# sra_board_2020.net
KiCad netlist of a schematic drawn in EAGLE
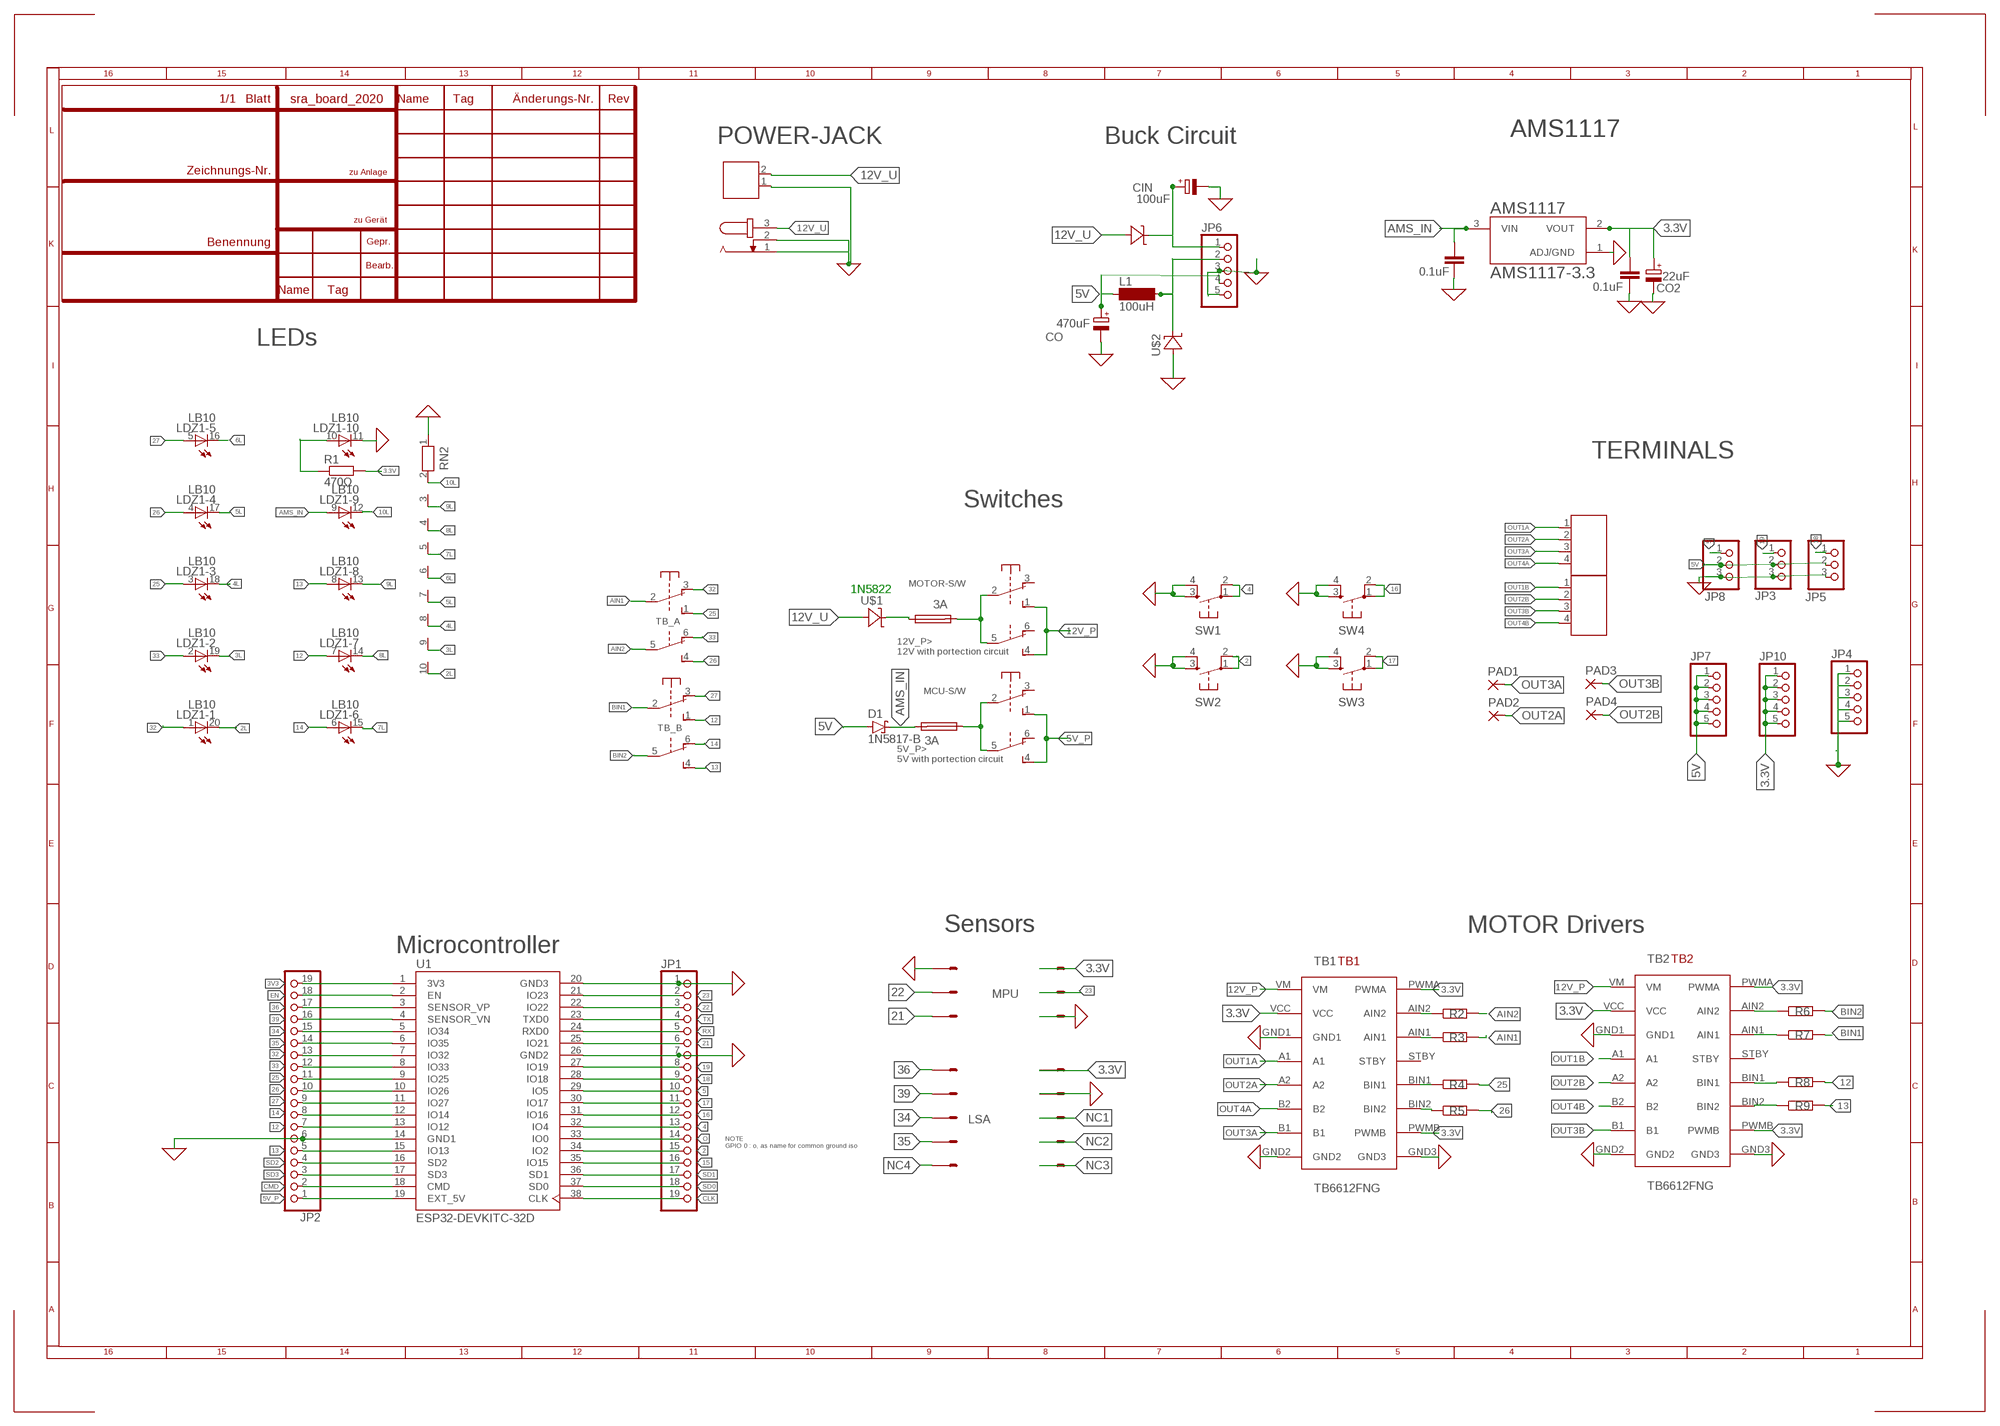
[diagram p0: schematic, sheet 1]

(export (version "E")
  (design (tool "Eeschema 10.0.6"))
  (components
    (comp (ref "12V")
      (value "691131710002")
      (footprint "eagle-import:691131710002")
      (libsource (lib "eagle-import") (part "691131710002"))
    )
    (comp (ref "AMS1117")
      (value "AMS1117-3.3")
      (footprint "eagle-import:SOT229P700X180-4N")
      (fields (field (name "MF") "Advanced Monolithic Systems"))
      (libsource (lib "eagle-import") (part "AMS1117-3.3"))
    )
    (comp (ref "CIN")
      (value "100uF")
      (footprint "eagle-import:E2,5-6")
      (libsource (lib "eagle-import") (part "CPOL-EUE2.5-6"))
    )
    (comp (ref "CIN1")
      (value "0.1uF")
      (footprint "eagle-import:C5B2.5")
      (libsource (lib "eagle-import") (part "C5/2.5"))
    )
    (comp (ref "CO")
      (value "470uF")
      (footprint "eagle-import:E3,5-10")
      (libsource (lib "eagle-import") (part "CPOL-EUE3.5-10"))
    )
    (comp (ref "CO1")
      (value "0.1uF")
      (footprint "eagle-import:C5B2.5")
      (libsource (lib "eagle-import") (part "C5/2.5"))
    )
    (comp (ref "CO2")
      (value "22uF")
      (footprint "eagle-import:E2,5-6")
      (libsource (lib "eagle-import") (part "CPOL-EUE2.5-6"))
    )
    (comp (ref "D1")
      (value "1N5817-B")
      (footprint "eagle-import:DO41-7.6")
      (libsource (lib "eagle-import") (part "1N5817-B"))
    )
    (comp (ref "F2")
      (value "3A")
      (footprint "eagle-import:SH25")
      (fields (field (name "MF") "SCHURTER") (field (name "MPN") "0031.8211"))
      (libsource (lib "eagle-import") (part "SH25"))
    )
    (comp (ref "F3")
      (value "3A")
      (footprint "eagle-import:SH25")
      (fields (field (name "MF") "SCHURTER") (field (name "MPN") "0031.8211"))
      (libsource (lib "eagle-import") (part "SH25"))
    )
    (comp (ref "J1")
      (value "691131710004")
      (footprint "eagle-import:691131710004")
      (libsource (lib "eagle-import") (part "691131710004"))
    )
    (comp (ref "J2")
      (value "691131710004")
      (footprint "eagle-import:691131710004")
      (libsource (lib "eagle-import") (part "691131710004"))
    )
    (comp (ref "JP1")
      (value "PINHD-1X19")
      (footprint "eagle-import:1X19")
      (libsource (lib "eagle-import") (part "PINHD-1X19"))
    )
    (comp (ref "JP2")
      (value "PINHD-1X19")
      (footprint "eagle-import:1X19")
      (libsource (lib "eagle-import") (part "PINHD-1X19"))
    )
    (comp (ref "JP3")
      (value "PINHD-1X3")
      (footprint "eagle-import:1X03")
      (libsource (lib "eagle-import") (part "PINHD-1X3"))
    )
    (comp (ref "JP4")
      (value "PINHD-1X5")
      (footprint "eagle-import:1X05")
      (libsource (lib "eagle-import") (part "pinhead_2_PINHD-1X5"))
    )
    (comp (ref "JP5")
      (value "PINHD-1X3")
      (footprint "eagle-import:1X03")
      (libsource (lib "eagle-import") (part "PINHD-1X3"))
    )
    (comp (ref "JP6")
      (value "PINHD-1X5")
      (footprint "eagle-import:1X05")
      (libsource (lib "eagle-import") (part "PINHD-1X5"))
    )
    (comp (ref "JP7")
      (value "PINHD-1X5")
      (footprint "eagle-import:1X05")
      (libsource (lib "eagle-import") (part "pinhead_2_PINHD-1X5"))
    )
    (comp (ref "JP8")
      (value "PINHD-1X3")
      (footprint "eagle-import:1X03")
      (libsource (lib "eagle-import") (part "PINHD-1X3"))
    )
    (comp (ref "JP10")
      (value "PINHD-1X5")
      (footprint "eagle-import:1X05")
      (libsource (lib "eagle-import") (part "pinhead_2_PINHD-1X5"))
    )
    (comp (ref "L1")
      (value "100uH")
      (footprint "eagle-import:SD12K100")
      (libsource (lib "eagle-import") (part "SD12K100"))
    )
    (comp (ref "LDZ1")
      (value "LB10")
      (footprint "eagle-import:LB10")
      (libsource (lib "eagle-import") (part "LB10"))
    )
    (comp (ref "LINE-SENSOR")
      (value "057-010-1")
      (footprint "eagle-import:057-010-1")
      (libsource (lib "eagle-import") (part "057-010-1"))
    )
    (comp (ref "MCU-S/W")
      (value "9077-2")
      (footprint "eagle-import:9077-2")
      (libsource (lib "eagle-import") (part "9077-2"))
    )
    (comp (ref "MOTOR-S/W")
      (value "9077-2")
      (footprint "eagle-import:9077-2")
      (libsource (lib "eagle-import") (part "9077-2"))
    )
    (comp (ref "PAD1")
      (value "SMD2")
      (footprint "eagle-import:SMD1,27-2,54")
      (libsource (lib "eagle-import") (part "SMD2"))
    )
    (comp (ref "PAD2")
      (value "SMD2")
      (footprint "eagle-import:SMD1,27-2,54")
      (libsource (lib "eagle-import") (part "SMD2"))
    )
    (comp (ref "PAD3")
      (value "SMD2")
      (footprint "eagle-import:SMD1,27-2,54")
      (libsource (lib "eagle-import") (part "SMD2"))
    )
    (comp (ref "PAD4")
      (value "SMD2")
      (footprint "eagle-import:SMD1,27-2,54")
      (libsource (lib "eagle-import") (part "SMD2"))
    )
    (comp (ref "POWER-JACK")
      (value "JACK-PLUG1")
      (footprint "eagle-import:SPC4078")
      (libsource (lib "eagle-import") (part "JACK-PLUG1"))
    )
    (comp (ref "R1")
      (value "470Ω")
      (footprint "eagle-import:0204_7")
      (libsource (lib "eagle-import") (part "R-EU_0204/7"))
    )
    (comp (ref "R2")
      (value "1KΩ")
      (footprint "eagle-import:0204_7")
      (libsource (lib "eagle-import") (part "R-EU_0204/7"))
    )
    (comp (ref "R3")
      (value "1KΩ")
      (footprint "eagle-import:0204_7")
      (libsource (lib "eagle-import") (part "R-EU_0204/7"))
    )
    (comp (ref "R4")
      (value "1KΩ")
      (footprint "eagle-import:0204_7")
      (libsource (lib "eagle-import") (part "R-EU_0204/7"))
    )
    (comp (ref "R5")
      (value "1KΩ")
      (footprint "eagle-import:0204_7")
      (libsource (lib "eagle-import") (part "R-EU_0204/7"))
    )
    (comp (ref "R6")
      (value "1KΩ")
      (footprint "eagle-import:0204_7")
      (libsource (lib "eagle-import") (part "R-EU_0204/7"))
    )
    (comp (ref "R7")
      (value "1KΩ")
      (footprint "eagle-import:0204_7")
      (libsource (lib "eagle-import") (part "R-EU_0204/7"))
    )
    (comp (ref "R8")
      (value "1KΩ")
      (footprint "eagle-import:0204_7")
      (libsource (lib "eagle-import") (part "R-EU_0204/7"))
    )
    (comp (ref "R9")
      (value "1KΩ")
      (footprint "eagle-import:0204_7")
      (libsource (lib "eagle-import") (part "R-EU_0204/7"))
    )
    (comp (ref "RN2")
      (value "RN09")
      (footprint "eagle-import:RN-10")
      (libsource (lib "eagle-import") (part "RN09"))
    )
    (comp (ref "SW1")
      (value "DTS-6")
      (footprint "eagle-import:DTS-6")
      (libsource (lib "eagle-import") (part "DTS-6"))
    )
    (comp (ref "SW2")
      (value "DTS-6")
      (footprint "eagle-import:DTS-6")
      (libsource (lib "eagle-import") (part "DTS-6"))
    )
    (comp (ref "SW3")
      (value "DTS-6")
      (footprint "eagle-import:DTS-6")
      (libsource (lib "eagle-import") (part "DTS-6"))
    )
    (comp (ref "SW4")
      (value "DTS-6")
      (footprint "eagle-import:DTS-6")
      (libsource (lib "eagle-import") (part "DTS-6"))
    )
    (comp (ref "TB1")
      (value "TB6612FNG")
      (footprint "eagle-import:TB6612FNG")
      (libsource (lib "eagle-import") (part "TB6612FNG"))
    )
    (comp (ref "TB2")
      (value "TB6612FNG")
      (footprint "eagle-import:TB6612FNG")
      (libsource (lib "eagle-import") (part "TB6612FNG"))
    )
    (comp (ref "TB_A")
      (value "9077-2")
      (footprint "eagle-import:9077-2")
      (libsource (lib "eagle-import") (part "9077-2"))
    )
    (comp (ref "TB_B")
      (value "9077-2")
      (footprint "eagle-import:9077-2")
      (libsource (lib "eagle-import") (part "9077-2"))
    )
    (comp (ref "U$1")
      (value "1N5399_SQUARE")
      (footprint "eagle-import:C2673")
      (libsource (lib "eagle-import") (part "1N5399_SQUARE"))
    )
    (comp (ref "U$2")
      (value "1N5399_SQUARE")
      (footprint "eagle-import:C2673")
      (libsource (lib "eagle-import") (part "1N5399_SQUARE"))
    )
    (comp (ref "U$3")
      (value "1N5399_ROUND")
      (footprint "eagle-import:D-10")
      (libsource (lib "eagle-import") (part "1N5399_ROUND"))
    )
    (comp (ref "U1")
      (value "ESP32-DEVKITC-32D")
      (footprint "eagle-import:MODULE_ESP32-DEVKITC-32D")
      (fields (field (name "MF") "Espressif Systems"))
      (libsource (lib "eagle-import") (part "ESP32-DEVKITC-32D"))
    )
    (comp (ref "X1")
      (value "057-006-1")
      (footprint "eagle-import:057-006-1")
      (libsource (lib "eagle-import") (part "057-006-1"))
    )
  )
  (nets
    (net (code "1") (name "2") (class "Default")
      (node (ref "JP1") (pin "15") (pinfunction "15_15") (pintype "passive"))
      (node (ref "SW2") (pin "1") (pinfunction "1_1") (pintype "passive"))
      (node (ref "SW2") (pin "2") (pinfunction "2_2") (pintype "passive"))
      (node (ref "U1") (pin "34") (pinfunction "IO2_34") (pintype "bidirectional"))
    )
    (net (code "2") (name "2L") (class "Default")
      (node (ref "LDZ1") (pin "20") (pinfunction "C_20") (pintype "passive"))
      (node (ref "RN2") (pin "10") (pinfunction "10_10") (pintype "passive"))
    )
    (net (code "3") (name "3.3V") (class "Default")
      (node (ref "AMS1117") (pin "2") (pinfunction "VOUT_2") (pintype "output"))
      (node (ref "CO1") (pin "2") (pinfunction "2_2") (pintype "passive"))
      (node (ref "CO2") (pin "+") (pinfunction "+_+") (pintype "passive"))
      (node (ref "JP10") (pin "1") (pinfunction "1_1") (pintype "passive"))
      (node (ref "JP10") (pin "2") (pinfunction "2_2") (pintype "passive"))
      (node (ref "JP10") (pin "3") (pinfunction "3_3") (pintype "passive"))
      (node (ref "JP10") (pin "4") (pinfunction "4_4") (pintype "passive"))
      (node (ref "JP10") (pin "5") (pinfunction "5_5") (pintype "passive"))
      (node (ref "LINE-SENSOR") (pin "2") (pinfunction "S_2") (pintype "passive"))
      (node (ref "R1") (pin "2") (pinfunction "2_2") (pintype "passive"))
      (node (ref "TB1") (pin "PWMA") (pinfunction "PWMA_PWMA") (pintype "bidirectional"))
      (node (ref "TB1") (pin "PWMB") (pinfunction "PWMB_PWMB") (pintype "bidirectional"))
      (node (ref "TB1") (pin "VCC") (pinfunction "VCC_VCC") (pintype "bidirectional"))
      (node (ref "TB2") (pin "PWMA") (pinfunction "PWMA_PWMA") (pintype "bidirectional"))
      (node (ref "TB2") (pin "PWMB") (pinfunction "PWMB_PWMB") (pintype "bidirectional"))
      (node (ref "TB2") (pin "VCC") (pinfunction "VCC_VCC") (pintype "bidirectional"))
      (node (ref "X1") (pin "2") (pinfunction "S_2") (pintype "passive"))
    )
    (net (code "4") (name "3L") (class "Default")
      (node (ref "LDZ1") (pin "19") (pinfunction "C_19") (pintype "passive"))
      (node (ref "RN2") (pin "9") (pinfunction "9_9") (pintype "passive"))
    )
    (net (code "5") (name "3V3") (class "Default")
      (node (ref "JP2") (pin "19") (pinfunction "19_19") (pintype "passive"))
      (node (ref "U1") (pin "1") (pinfunction "3V3_1") (pintype "power_in"))
    )
    (net (code "6") (name "4") (class "Default")
      (node (ref "JP1") (pin "13") (pinfunction "13_13") (pintype "passive"))
      (node (ref "SW1") (pin "1") (pinfunction "1_1") (pintype "passive"))
      (node (ref "SW1") (pin "2") (pinfunction "2_2") (pintype "passive"))
      (node (ref "U1") (pin "32") (pinfunction "IO4_32") (pintype "bidirectional"))
    )
    (net (code "7") (name "4L") (class "Default")
      (node (ref "LDZ1") (pin "18") (pinfunction "C_18") (pintype "passive"))
      (node (ref "RN2") (pin "8") (pinfunction "8_8") (pintype "passive"))
    )
    (net (code "8") (name "5") (class "Default")
      (node (ref "JP1") (pin "10") (pinfunction "10_10") (pintype "passive"))
      (node (ref "JP8") (pin "1") (pinfunction "1_1") (pintype "passive"))
      (node (ref "U1") (pin "29") (pinfunction "IO5_29") (pintype "bidirectional"))
    )
    (net (code "9") (name "5L") (class "Default")
      (node (ref "LDZ1") (pin "17") (pinfunction "C_17") (pintype "passive"))
      (node (ref "RN2") (pin "7") (pinfunction "7_7") (pintype "passive"))
    )
    (net (code "10") (name "5V") (class "Default")
      (node (ref "CO") (pin "+") (pinfunction "+_+") (pintype "passive"))
      (node (ref "D1") (pin "A") (pinfunction "A_A") (pintype "passive"))
      (node (ref "JP3") (pin "2") (pinfunction "2_2") (pintype "passive"))
      (node (ref "JP5") (pin "2") (pinfunction "2_2") (pintype "passive"))
      (node (ref "JP6") (pin "4") (pinfunction "4_4") (pintype "passive"))
      (node (ref "JP7") (pin "1") (pinfunction "1_1") (pintype "passive"))
      (node (ref "JP7") (pin "2") (pinfunction "2_2") (pintype "passive"))
      (node (ref "JP7") (pin "3") (pinfunction "3_3") (pintype "passive"))
      (node (ref "JP7") (pin "4") (pinfunction "4_4") (pintype "passive"))
      (node (ref "JP7") (pin "5") (pinfunction "5_5") (pintype "passive"))
      (node (ref "JP8") (pin "2") (pinfunction "2_2") (pintype "passive"))
      (node (ref "L1") (pin "1") (pinfunction "1_1") (pintype "passive"))
    )
    (net (code "11") (name "5V_P") (class "Default")
      (node (ref "JP2") (pin "1") (pinfunction "1_1") (pintype "passive"))
      (node (ref "MCU-S/W") (pin "1") (pinfunction "S_1") (pintype "passive"))
      (node (ref "MCU-S/W") (pin "4") (pinfunction "S_4") (pintype "passive"))
      (node (ref "U1") (pin "19") (pinfunction "EXT_5V_19") (pintype "power_in"))
    )
    (net (code "12") (name "6L") (class "Default")
      (node (ref "LDZ1") (pin "16") (pinfunction "C_16") (pintype "passive"))
      (node (ref "RN2") (pin "6") (pinfunction "6_6") (pintype "passive"))
    )
    (net (code "13") (name "7L") (class "Default")
      (node (ref "LDZ1") (pin "15") (pinfunction "C_15") (pintype "passive"))
      (node (ref "RN2") (pin "5") (pinfunction "5_5") (pintype "passive"))
    )
    (net (code "14") (name "8L") (class "Default")
      (node (ref "LDZ1") (pin "14") (pinfunction "C_14") (pintype "passive"))
      (node (ref "RN2") (pin "4") (pinfunction "4_4") (pintype "passive"))
    )
    (net (code "15") (name "9L") (class "Default")
      (node (ref "LDZ1") (pin "13") (pinfunction "C_13") (pintype "passive"))
      (node (ref "RN2") (pin "3") (pinfunction "3_3") (pintype "passive"))
    )
    (net (code "16") (name "10L") (class "Default")
      (node (ref "LDZ1") (pin "12") (pinfunction "C_12") (pintype "passive"))
      (node (ref "RN2") (pin "2") (pinfunction "2_2") (pintype "passive"))
    )
    (net (code "17") (name "12") (class "Default")
      (node (ref "JP2") (pin "7") (pinfunction "7_7") (pintype "passive"))
      (node (ref "LDZ1") (pin "7") (pinfunction "A_7") (pintype "passive"))
      (node (ref "R8") (pin "2") (pinfunction "2_2") (pintype "passive"))
      (node (ref "TB_B") (pin "1") (pinfunction "S_1") (pintype "passive"))
      (node (ref "U1") (pin "13") (pinfunction "IO12_13") (pintype "bidirectional"))
    )
    (net (code "18") (name "12V_P") (class "Default")
      (node (ref "MOTOR-S/W") (pin "1") (pinfunction "S_1") (pintype "passive"))
      (node (ref "MOTOR-S/W") (pin "4") (pinfunction "S_4") (pintype "passive"))
      (node (ref "TB1") (pin "VM") (pinfunction "VM_VM") (pintype "bidirectional"))
      (node (ref "TB2") (pin "VM") (pinfunction "VM_VM") (pintype "bidirectional"))
    )
    (net (code "19") (name "12V_U") (class "Default")
      (node (ref "12V") (pin "2") (pinfunction "2_2") (pintype "passive"))
      (node (ref "POWER-JACK") (pin "3") (pinfunction "3_3") (pintype "passive"))
      (node (ref "U$1") (pin "A") (pinfunction "A_A") (pintype "passive"))
      (node (ref "U$3") (pin "A") (pinfunction "A_A") (pintype "passive"))
    )
    (net (code "20") (name "13") (class "Default")
      (node (ref "JP2") (pin "5") (pinfunction "5_5") (pintype "passive"))
      (node (ref "LDZ1") (pin "8") (pinfunction "A_8") (pintype "passive"))
      (node (ref "R9") (pin "2") (pinfunction "2_2") (pintype "passive"))
      (node (ref "TB_B") (pin "4") (pinfunction "S_4") (pintype "passive"))
      (node (ref "U1") (pin "15") (pinfunction "IO13_15") (pintype "bidirectional"))
    )
    (net (code "21") (name "14") (class "Default")
      (node (ref "JP2") (pin "8") (pinfunction "8_8") (pintype "passive"))
      (node (ref "LDZ1") (pin "6") (pinfunction "A_6") (pintype "passive"))
      (node (ref "TB_B") (pin "6") (pinfunction "O_6") (pintype "passive"))
      (node (ref "U1") (pin "12") (pinfunction "IO14_12") (pintype "bidirectional"))
    )
    (net (code "22") (name "15") (class "Default")
      (node (ref "JP1") (pin "16") (pinfunction "16_16") (pintype "passive"))
      (node (ref "U1") (pin "35") (pinfunction "IO15_35") (pintype "bidirectional"))
    )
    (net (code "23") (name "16") (class "Default")
      (node (ref "JP1") (pin "12") (pinfunction "12_12") (pintype "passive"))
      (node (ref "SW4") (pin "1") (pinfunction "1_1") (pintype "passive"))
      (node (ref "SW4") (pin "2") (pinfunction "2_2") (pintype "passive"))
      (node (ref "U1") (pin "31") (pinfunction "IO16_31") (pintype "bidirectional"))
    )
    (net (code "24") (name "17") (class "Default")
      (node (ref "JP1") (pin "11") (pinfunction "11_11") (pintype "passive"))
      (node (ref "SW3") (pin "1") (pinfunction "1_1") (pintype "passive"))
      (node (ref "SW3") (pin "2") (pinfunction "2_2") (pintype "passive"))
      (node (ref "U1") (pin "30") (pinfunction "IO17_30") (pintype "bidirectional"))
    )
    (net (code "25") (name "18") (class "Default")
      (node (ref "JP1") (pin "9") (pinfunction "9_9") (pintype "passive"))
      (node (ref "JP5") (pin "1") (pinfunction "1_1") (pintype "passive"))
      (node (ref "U1") (pin "28") (pinfunction "IO18_28") (pintype "bidirectional"))
    )
    (net (code "26") (name "19") (class "Default")
      (node (ref "JP1") (pin "8") (pinfunction "8_8") (pintype "passive"))
      (node (ref "JP3") (pin "1") (pinfunction "1_1") (pintype "passive"))
      (node (ref "U1") (pin "27") (pinfunction "IO19_27") (pintype "bidirectional"))
    )
    (net (code "27") (name "21") (class "Default")
      (node (ref "JP1") (pin "6") (pinfunction "6_6") (pintype "passive"))
      (node (ref "U1") (pin "25") (pinfunction "IO21_25") (pintype "bidirectional"))
      (node (ref "X1") (pin "5") (pinfunction "S_5") (pintype "passive"))
    )
    (net (code "28") (name "22") (class "Default")
      (node (ref "JP1") (pin "3") (pinfunction "3_3") (pintype "passive"))
      (node (ref "U1") (pin "22") (pinfunction "IO22_22") (pintype "bidirectional"))
      (node (ref "X1") (pin "3") (pinfunction "S_3") (pintype "passive"))
    )
    (net (code "29") (name "23") (class "Default")
      (node (ref "JP1") (pin "2") (pinfunction "2_2") (pintype "passive"))
      (node (ref "U1") (pin "21") (pinfunction "IO23_21") (pintype "bidirectional"))
      (node (ref "X1") (pin "4") (pinfunction "S_4") (pintype "passive"))
    )
    (net (code "30") (name "25") (class "Default")
      (node (ref "JP2") (pin "11") (pinfunction "11_11") (pintype "passive"))
      (node (ref "LDZ1") (pin "3") (pinfunction "A_3") (pintype "passive"))
      (node (ref "R4") (pin "2") (pinfunction "2_2") (pintype "passive"))
      (node (ref "TB_A") (pin "1") (pinfunction "S_1") (pintype "passive"))
      (node (ref "U1") (pin "9") (pinfunction "IO25_9") (pintype "bidirectional"))
    )
    (net (code "31") (name "26") (class "Default")
      (node (ref "JP2") (pin "10") (pinfunction "10_10") (pintype "passive"))
      (node (ref "LDZ1") (pin "4") (pinfunction "A_4") (pintype "passive"))
      (node (ref "R5") (pin "2") (pinfunction "2_2") (pintype "passive"))
      (node (ref "TB_A") (pin "4") (pinfunction "S_4") (pintype "passive"))
      (node (ref "U1") (pin "10") (pinfunction "IO26_10") (pintype "bidirectional"))
    )
    (net (code "32") (name "27") (class "Default")
      (node (ref "JP2") (pin "9") (pinfunction "9_9") (pintype "passive"))
      (node (ref "LDZ1") (pin "5") (pinfunction "A_5") (pintype "passive"))
      (node (ref "TB_B") (pin "3") (pinfunction "O_3") (pintype "passive"))
      (node (ref "U1") (pin "11") (pinfunction "IO27_11") (pintype "bidirectional"))
    )
    (net (code "33") (name "32") (class "Default")
      (node (ref "JP2") (pin "13") (pinfunction "13_13") (pintype "passive"))
      (node (ref "LDZ1") (pin "1") (pinfunction "A_1") (pintype "passive"))
      (node (ref "TB_A") (pin "3") (pinfunction "O_3") (pintype "passive"))
      (node (ref "U1") (pin "7") (pinfunction "IO32_7") (pintype "bidirectional"))
    )
    (net (code "34") (name "33") (class "Default")
      (node (ref "JP2") (pin "12") (pinfunction "12_12") (pintype "passive"))
      (node (ref "LDZ1") (pin "2") (pinfunction "A_2") (pintype "passive"))
      (node (ref "TB_A") (pin "6") (pinfunction "O_6") (pintype "passive"))
      (node (ref "U1") (pin "8") (pinfunction "IO33_8") (pintype "bidirectional"))
    )
    (net (code "35") (name "34") (class "Default")
      (node (ref "JP2") (pin "15") (pinfunction "15_15") (pintype "passive"))
      (node (ref "LINE-SENSOR") (pin "5") (pinfunction "S_5") (pintype "passive"))
      (node (ref "U1") (pin "5") (pinfunction "IO34_5") (pintype "bidirectional"))
    )
    (net (code "36") (name "35") (class "Default")
      (node (ref "JP2") (pin "14") (pinfunction "14_14") (pintype "passive"))
      (node (ref "LINE-SENSOR") (pin "7") (pinfunction "S_7") (pintype "passive"))
      (node (ref "U1") (pin "6") (pinfunction "IO35_6") (pintype "bidirectional"))
    )
    (net (code "37") (name "36") (class "Default")
      (node (ref "JP2") (pin "17") (pinfunction "17_17") (pintype "passive"))
      (node (ref "LINE-SENSOR") (pin "1") (pinfunction "S_1") (pintype "passive"))
      (node (ref "U1") (pin "3") (pinfunction "SENSOR_VP_3") (pintype "input"))
    )
    (net (code "38") (name "39") (class "Default")
      (node (ref "JP2") (pin "16") (pinfunction "16_16") (pintype "passive"))
      (node (ref "LINE-SENSOR") (pin "3") (pinfunction "S_3") (pintype "passive"))
      (node (ref "U1") (pin "4") (pinfunction "SENSOR_VN_4") (pintype "input"))
    )
    (net (code "39") (name "AIN1") (class "Default")
      (node (ref "R3") (pin "2") (pinfunction "2_2") (pintype "passive"))
      (node (ref "TB_A") (pin "2") (pinfunction "P_2") (pintype "passive"))
    )
    (net (code "40") (name "AIN2") (class "Default")
      (node (ref "R2") (pin "2") (pinfunction "2_2") (pintype "passive"))
      (node (ref "TB_A") (pin "5") (pinfunction "P_5") (pintype "passive"))
    )
    (net (code "41") (name "AMS_IN") (class "Default")
      (node (ref "AMS1117") (pin "3") (pinfunction "VIN_3") (pintype "input"))
      (node (ref "CIN1") (pin "2") (pinfunction "2_2") (pintype "passive"))
      (node (ref "D1") (pin "C") (pinfunction "C_C") (pintype "passive"))
      (node (ref "F2") (pin "2") (pinfunction "2_2") (pintype "passive"))
      (node (ref "LDZ1") (pin "9") (pinfunction "A_9") (pintype "passive"))
    )
    (net (code "42") (name "BIN1") (class "Default")
      (node (ref "R7") (pin "2") (pinfunction "2_2") (pintype "passive"))
      (node (ref "TB_B") (pin "2") (pinfunction "P_2") (pintype "passive"))
    )
    (net (code "43") (name "BIN2") (class "Default")
      (node (ref "R6") (pin "2") (pinfunction "2_2") (pintype "passive"))
      (node (ref "TB_B") (pin "5") (pinfunction "P_5") (pintype "passive"))
    )
    (net (code "44") (name "CLK") (class "Default")
      (node (ref "JP1") (pin "19") (pinfunction "19_19") (pintype "passive"))
      (node (ref "U1") (pin "38") (pinfunction "CLK_38") (pintype "input"))
    )
    (net (code "45") (name "CMD") (class "Default")
      (node (ref "JP2") (pin "2") (pinfunction "2_2") (pintype "passive"))
      (node (ref "U1") (pin "18") (pinfunction "CMD_18") (pintype "bidirectional"))
    )
    (net (code "46") (name "EN") (class "Default")
      (node (ref "JP2") (pin "18") (pinfunction "18_18") (pintype "passive"))
      (node (ref "U1") (pin "2") (pinfunction "EN_2") (pintype "input"))
    )
    (net (code "47") (name "GND") (class "Default")
      (node (ref "12V") (pin "1") (pinfunction "1_1") (pintype "passive"))
      (node (ref "AMS1117") (pin "1") (pinfunction "ADJ/GND_1") (pintype "power_in"))
      (node (ref "CIN") (pin "-") (pinfunction "-_-") (pintype "passive"))
      (node (ref "CIN1") (pin "1") (pinfunction "1_1") (pintype "passive"))
      (node (ref "CO") (pin "-") (pinfunction "-_-") (pintype "passive"))
      (node (ref "CO1") (pin "1") (pinfunction "1_1") (pintype "passive"))
      (node (ref "CO2") (pin "-") (pinfunction "-_-") (pintype "passive"))
      (node (ref "JP1") (pin "1") (pinfunction "1_1") (pintype "passive"))
      (node (ref "JP1") (pin "7") (pinfunction "7_7") (pintype "passive"))
      (node (ref "JP2") (pin "6") (pinfunction "6_6") (pintype "passive"))
      (node (ref "JP3") (pin "3") (pinfunction "3_3") (pintype "passive"))
      (node (ref "JP4") (pin "1") (pinfunction "1_1") (pintype "passive"))
      (node (ref "JP4") (pin "2") (pinfunction "2_2") (pintype "passive"))
      (node (ref "JP4") (pin "3") (pinfunction "3_3") (pintype "passive"))
      (node (ref "JP4") (pin "4") (pinfunction "4_4") (pintype "passive"))
      (node (ref "JP4") (pin "5") (pinfunction "5_5") (pintype "passive"))
      (node (ref "JP5") (pin "3") (pinfunction "3_3") (pintype "passive"))
      (node (ref "JP6") (pin "3") (pinfunction "3_3") (pintype "passive"))
      (node (ref "JP6") (pin "5") (pinfunction "5_5") (pintype "passive"))
      (node (ref "JP8") (pin "3") (pinfunction "3_3") (pintype "passive"))
      (node (ref "LDZ1") (pin "11") (pinfunction "C_11") (pintype "passive"))
      (node (ref "LINE-SENSOR") (pin "4") (pinfunction "S_4") (pintype "passive"))
      (node (ref "POWER-JACK") (pin "1") (pinfunction "1_1") (pintype "passive"))
      (node (ref "POWER-JACK") (pin "2") (pinfunction "2_2") (pintype "passive"))
      (node (ref "RN2") (pin "1") (pinfunction "1_1") (pintype "passive"))
      (node (ref "SW1") (pin "3") (pinfunction "3_3") (pintype "passive"))
      (node (ref "SW1") (pin "4") (pinfunction "4_4") (pintype "passive"))
      (node (ref "SW2") (pin "3") (pinfunction "3_3") (pintype "passive"))
      (node (ref "SW2") (pin "4") (pinfunction "4_4") (pintype "passive"))
      (node (ref "SW3") (pin "3") (pinfunction "3_3") (pintype "passive"))
      (node (ref "SW3") (pin "4") (pinfunction "4_4") (pintype "passive"))
      (node (ref "SW4") (pin "3") (pinfunction "3_3") (pintype "passive"))
      (node (ref "SW4") (pin "4") (pinfunction "4_4") (pintype "passive"))
      (node (ref "TB1") (pin "GND1") (pinfunction "GND1_GND1") (pintype "bidirectional"))
      (node (ref "TB1") (pin "GND2") (pinfunction "GND2_GND2") (pintype "bidirectional"))
      (node (ref "TB1") (pin "GND3") (pinfunction "GND3_GND3") (pintype "bidirectional"))
      (node (ref "TB2") (pin "GND1") (pinfunction "GND1_GND1") (pintype "bidirectional"))
      (node (ref "TB2") (pin "GND2") (pinfunction "GND2_GND2") (pintype "bidirectional"))
      (node (ref "TB2") (pin "GND3") (pinfunction "GND3_GND3") (pintype "bidirectional"))
      (node (ref "U$2") (pin "A") (pinfunction "A_A") (pintype "passive"))
      (node (ref "U1") (pin "14") (pinfunction "GND1_14") (pintype "power_in"))
      (node (ref "U1") (pin "20") (pinfunction "GND3_20") (pintype "power_in"))
      (node (ref "U1") (pin "26") (pinfunction "GND2_26") (pintype "power_in"))
      (node (ref "X1") (pin "1") (pinfunction "S_1") (pintype "passive"))
      (node (ref "X1") (pin "6") (pinfunction "S_6") (pintype "passive"))
    )
    (net (code "48") (name "NC1") (class "Default")
      (node (ref "LINE-SENSOR") (pin "6") (pinfunction "S_6") (pintype "passive"))
    )
    (net (code "49") (name "NC2") (class "Default")
      (node (ref "LINE-SENSOR") (pin "8") (pinfunction "S_8") (pintype "passive"))
    )
    (net (code "50") (name "NC3") (class "Default")
      (node (ref "LINE-SENSOR") (pin "10") (pinfunction "S_10") (pintype "passive"))
    )
    (net (code "51") (name "NC4") (class "Default")
      (node (ref "LINE-SENSOR") (pin "9") (pinfunction "S_9") (pintype "passive"))
    )
    (net (code "52") (name "Net-(CIN-Pad+)") (class "Default")
      (node (ref "CIN") (pin "+") (pinfunction "+_+") (pintype "passive"))
      (node (ref "JP6") (pin "1") (pinfunction "1_1") (pintype "passive"))
      (node (ref "U$3") (pin "C") (pinfunction "C_C") (pintype "passive"))
    )
    (net (code "53") (name "Net-(F3-Pad1)") (class "Default")
      (node (ref "F3") (pin "1") (pinfunction "1_1") (pintype "passive"))
      (node (ref "U$1") (pin "C") (pinfunction "C_C") (pintype "passive"))
    )
    (net (code "54") (name "Net-(JP6-Pad2)") (class "Default")
      (node (ref "JP6") (pin "2") (pinfunction "2_2") (pintype "passive"))
      (node (ref "L1") (pin "2") (pinfunction "2_2") (pintype "passive"))
      (node (ref "U$2") (pin "C") (pinfunction "C_C") (pintype "passive"))
    )
    (net (code "55") (name "Net-(LDZ1B-A)") (class "Default")
      (node (ref "LDZ1") (pin "10") (pinfunction "A_10") (pintype "passive"))
      (node (ref "R1") (pin "1") (pinfunction "1_1") (pintype "passive"))
    )
    (net (code "56") (name "Net-(MCU-S/WA-P)") (class "Default")
      (node (ref "F2") (pin "1") (pinfunction "1_1") (pintype "passive"))
      (node (ref "MCU-S/W") (pin "2") (pinfunction "P_2") (pintype "passive"))
      (node (ref "MCU-S/W") (pin "5") (pinfunction "P_5") (pintype "passive"))
    )
    (net (code "57") (name "Net-(MOTOR-S/WA-P)") (class "Default")
      (node (ref "F3") (pin "2") (pinfunction "2_2") (pintype "passive"))
      (node (ref "MOTOR-S/W") (pin "2") (pinfunction "P_2") (pintype "passive"))
      (node (ref "MOTOR-S/W") (pin "5") (pinfunction "P_5") (pintype "passive"))
    )
    (net (code "58") (name "Net-(R2-Pad1)") (class "Default")
      (node (ref "R2") (pin "1") (pinfunction "1_1") (pintype "passive"))
      (node (ref "TB1") (pin "AIN2") (pinfunction "AIN2_AIN2") (pintype "bidirectional"))
    )
    (net (code "59") (name "Net-(R3-Pad1)") (class "Default")
      (node (ref "R3") (pin "1") (pinfunction "1_1") (pintype "passive"))
      (node (ref "TB1") (pin "AIN1") (pinfunction "AIN1_AIN1") (pintype "bidirectional"))
    )
    (net (code "60") (name "Net-(R4-Pad1)") (class "Default")
      (node (ref "R4") (pin "1") (pinfunction "1_1") (pintype "passive"))
      (node (ref "TB1") (pin "BIN1") (pinfunction "BIN1_BIN1") (pintype "bidirectional"))
    )
    (net (code "61") (name "Net-(R5-Pad1)") (class "Default")
      (node (ref "R5") (pin "1") (pinfunction "1_1") (pintype "passive"))
      (node (ref "TB1") (pin "BIN2") (pinfunction "BIN2_BIN2") (pintype "bidirectional"))
    )
    (net (code "62") (name "Net-(R6-Pad1)") (class "Default")
      (node (ref "R6") (pin "1") (pinfunction "1_1") (pintype "passive"))
      (node (ref "TB2") (pin "AIN2") (pinfunction "AIN2_AIN2") (pintype "bidirectional"))
    )
    (net (code "63") (name "Net-(R7-Pad1)") (class "Default")
      (node (ref "R7") (pin "1") (pinfunction "1_1") (pintype "passive"))
      (node (ref "TB2") (pin "AIN1") (pinfunction "AIN1_AIN1") (pintype "bidirectional"))
    )
    (net (code "64") (name "Net-(R8-Pad1)") (class "Default")
      (node (ref "R8") (pin "1") (pinfunction "1_1") (pintype "passive"))
      (node (ref "TB2") (pin "BIN1") (pinfunction "BIN1_BIN1") (pintype "bidirectional"))
    )
    (net (code "65") (name "Net-(R9-Pad1)") (class "Default")
      (node (ref "R9") (pin "1") (pinfunction "1_1") (pintype "passive"))
      (node (ref "TB2") (pin "BIN2") (pinfunction "BIN2_BIN2") (pintype "bidirectional"))
    )
    (net (code "66") (name "O") (class "Default")
      (node (ref "JP1") (pin "14") (pinfunction "14_14") (pintype "passive"))
      (node (ref "U1") (pin "33") (pinfunction "IO0_33") (pintype "bidirectional"))
    )
    (net (code "67") (name "OUT1A") (class "Default")
      (node (ref "J1") (pin "1") (pinfunction "1_1") (pintype "passive"))
      (node (ref "TB1") (pin "A1") (pinfunction "A1_A1") (pintype "bidirectional"))
    )
    (net (code "68") (name "OUT1B") (class "Default")
      (node (ref "J2") (pin "1") (pinfunction "1_1") (pintype "passive"))
      (node (ref "TB2") (pin "A1") (pinfunction "A1_A1") (pintype "bidirectional"))
    )
    (net (code "69") (name "OUT2A") (class "Default")
      (node (ref "J1") (pin "2") (pinfunction "2_2") (pintype "passive"))
      (node (ref "PAD2") (pin "1") (pinfunction "P_1") (pintype "passive"))
      (node (ref "TB1") (pin "A2") (pinfunction "A2_A2") (pintype "bidirectional"))
    )
    (net (code "70") (name "OUT2B") (class "Default")
      (node (ref "J2") (pin "2") (pinfunction "2_2") (pintype "passive"))
      (node (ref "PAD4") (pin "1") (pinfunction "P_1") (pintype "passive"))
      (node (ref "TB2") (pin "A2") (pinfunction "A2_A2") (pintype "bidirectional"))
    )
    (net (code "71") (name "OUT3A") (class "Default")
      (node (ref "J1") (pin "3") (pinfunction "3_3") (pintype "passive"))
      (node (ref "PAD1") (pin "1") (pinfunction "P_1") (pintype "passive"))
      (node (ref "TB1") (pin "B1") (pinfunction "B1_B1") (pintype "bidirectional"))
    )
    (net (code "72") (name "OUT3B") (class "Default")
      (node (ref "J2") (pin "3") (pinfunction "3_3") (pintype "passive"))
      (node (ref "PAD3") (pin "1") (pinfunction "P_1") (pintype "passive"))
      (node (ref "TB2") (pin "B1") (pinfunction "B1_B1") (pintype "bidirectional"))
    )
    (net (code "73") (name "OUT4A") (class "Default")
      (node (ref "J1") (pin "4") (pinfunction "4_4") (pintype "passive"))
      (node (ref "TB1") (pin "B2") (pinfunction "B2_B2") (pintype "bidirectional"))
    )
    (net (code "74") (name "OUT4B") (class "Default")
      (node (ref "J2") (pin "4") (pinfunction "4_4") (pintype "passive"))
      (node (ref "TB2") (pin "B2") (pinfunction "B2_B2") (pintype "bidirectional"))
    )
    (net (code "75") (name "RX") (class "Default")
      (node (ref "JP1") (pin "5") (pinfunction "5_5") (pintype "passive"))
      (node (ref "U1") (pin "24") (pinfunction "RXD0_24") (pintype "input"))
    )
    (net (code "76") (name "SD0") (class "Default")
      (node (ref "JP1") (pin "18") (pinfunction "18_18") (pintype "passive"))
      (node (ref "U1") (pin "37") (pinfunction "SD0_37") (pintype "bidirectional"))
    )
    (net (code "77") (name "SD1") (class "Default")
      (node (ref "JP1") (pin "17") (pinfunction "17_17") (pintype "passive"))
      (node (ref "U1") (pin "36") (pinfunction "SD1_36") (pintype "bidirectional"))
    )
    (net (code "78") (name "SD2") (class "Default")
      (node (ref "JP2") (pin "4") (pinfunction "4_4") (pintype "passive"))
      (node (ref "U1") (pin "16") (pinfunction "SD2_16") (pintype "bidirectional"))
    )
    (net (code "79") (name "SD3") (class "Default")
      (node (ref "JP2") (pin "3") (pinfunction "3_3") (pintype "passive"))
      (node (ref "U1") (pin "17") (pinfunction "SD3_17") (pintype "bidirectional"))
    )
    (net (code "80") (name "TX") (class "Default")
      (node (ref "JP1") (pin "4") (pinfunction "4_4") (pintype "passive"))
      (node (ref "U1") (pin "23") (pinfunction "TXD0_23") (pintype "output"))
    )
    (net (code "81") (name "unconnected-(MCU-S/WA-O-Pad3)") (class "Default")
      (node (ref "MCU-S/W") (pin "3") (pinfunction "O_3") (pintype "passive"))
    )
    (net (code "82") (name "unconnected-(MCU-S/WB-O-Pad6)") (class "Default")
      (node (ref "MCU-S/W") (pin "6") (pinfunction "O_6") (pintype "passive"))
    )
    (net (code "83") (name "unconnected-(MOTOR-S/WA-O-Pad3)") (class "Default")
      (node (ref "MOTOR-S/W") (pin "3") (pinfunction "O_3") (pintype "passive"))
    )
    (net (code "84") (name "unconnected-(MOTOR-S/WB-O-Pad6)") (class "Default")
      (node (ref "MOTOR-S/W") (pin "6") (pinfunction "O_6") (pintype "passive"))
    )
    (net (code "85") (name "unconnected-(TB1-PadSTBY)") (class "Default")
      (node (ref "TB1") (pin "STBY") (pinfunction "STBY_STBY") (pintype "bidirectional"))
    )
    (net (code "86") (name "unconnected-(TB2-PadSTBY)") (class "Default")
      (node (ref "TB2") (pin "STBY") (pinfunction "STBY_STBY") (pintype "bidirectional"))
    )
  )
)
